# USB_Type-C_Test.net
KiCad netlist of a schematic drawn in EAGLE
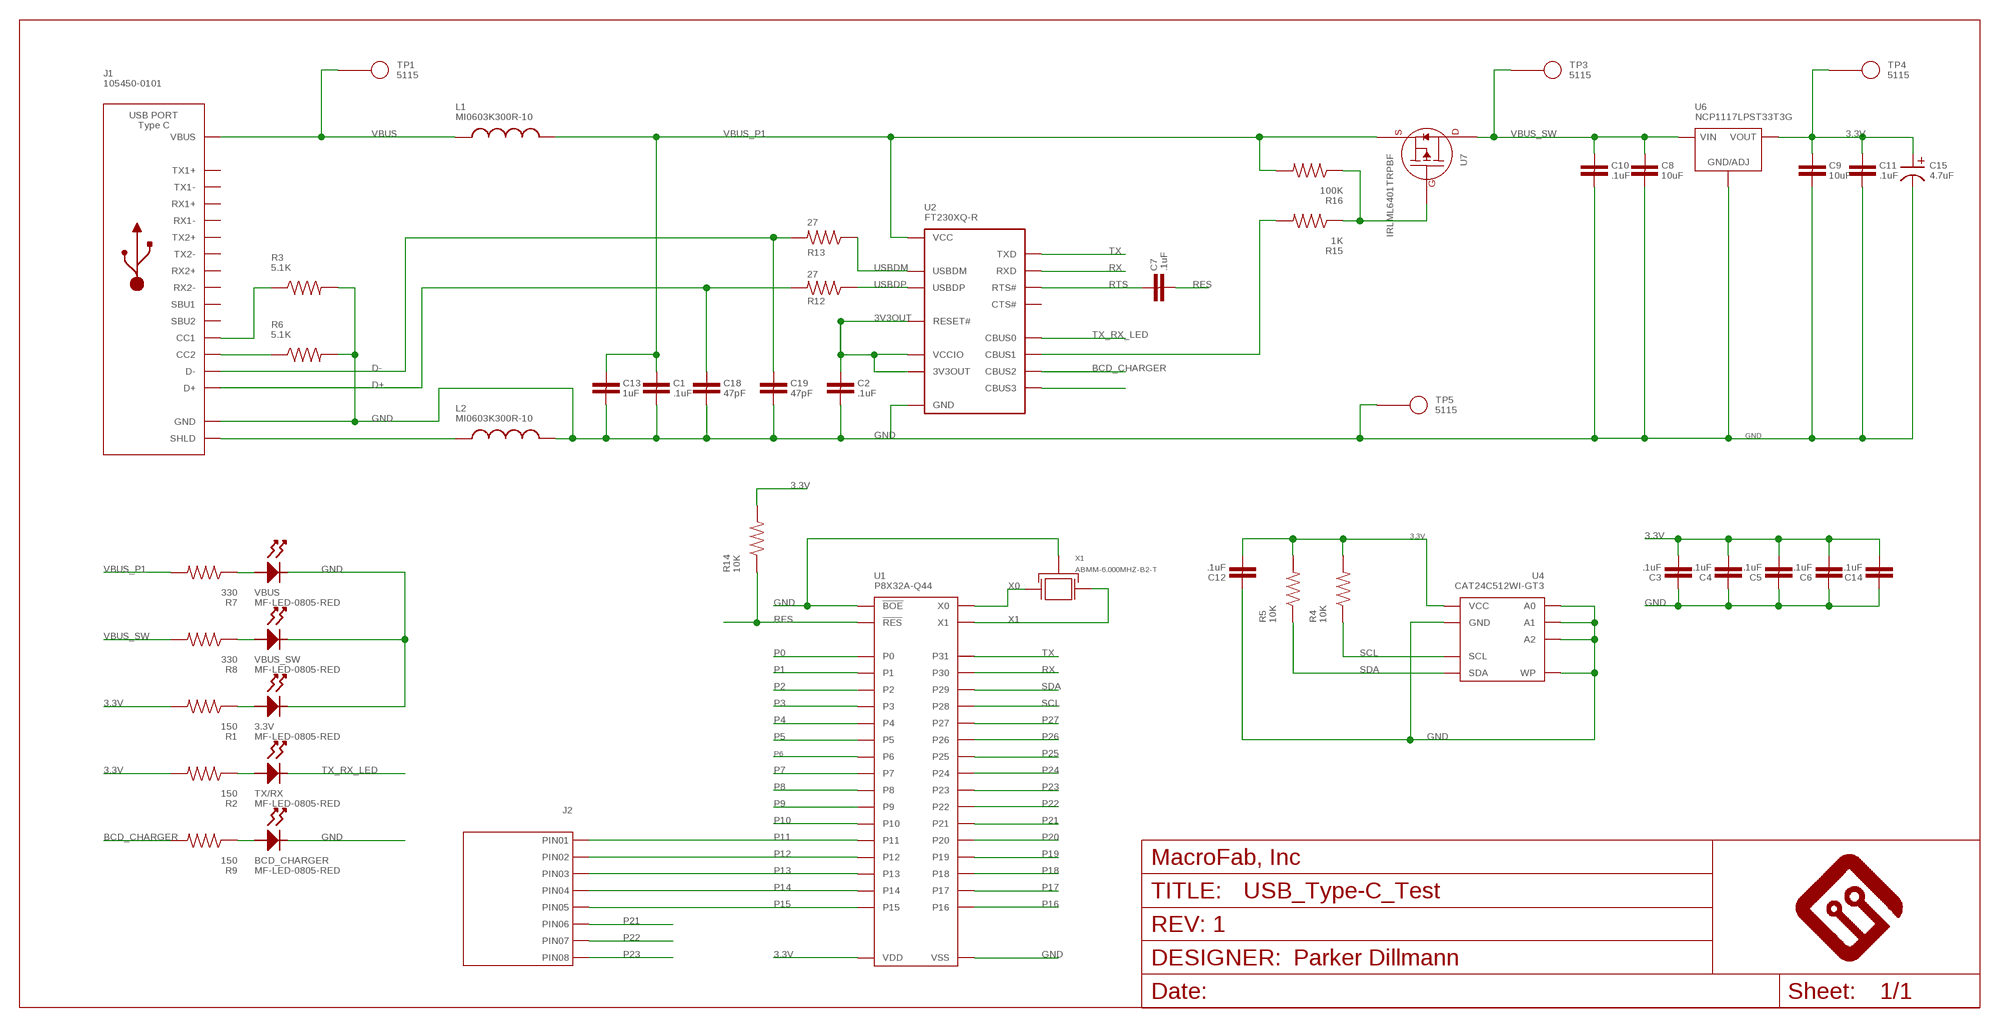
[diagram p0: schematic, sheet 1]

(export (version "E")
  (design (tool "Eeschema 10.0.6"))
  (components
    (comp (ref "3.3V")
      (value "MF-LED-0805-RED")
      (footprint "eagle-import:LED_0805")
      (libsource (lib "eagle-import") (part "LED_SINGLE_0805"))
    )
    (comp (ref "BCD_CHARGER")
      (value "MF-LED-0805-RED")
      (footprint "eagle-import:LED_0805")
      (libsource (lib "eagle-import") (part "LED_SINGLE_0805"))
    )
    (comp (ref "C1")
      (value ".1uF")
      (footprint "eagle-import:0603")
      (libsource (lib "eagle-import") (part "CAPACITOR_NON_POLAR_0603"))
    )
    (comp (ref "C2")
      (value ".1uF")
      (footprint "eagle-import:0603")
      (libsource (lib "eagle-import") (part "CAPACITOR_NON_POLAR_0603"))
    )
    (comp (ref "C3")
      (value ".1uF")
      (footprint "eagle-import:0603")
      (libsource (lib "eagle-import") (part "CAPACITOR_NON_POLAR_0603"))
    )
    (comp (ref "C4")
      (value ".1uF")
      (footprint "eagle-import:0603")
      (libsource (lib "eagle-import") (part "CAPACITOR_NON_POLAR_0603"))
    )
    (comp (ref "C5")
      (value ".1uF")
      (footprint "eagle-import:0603")
      (libsource (lib "eagle-import") (part "CAPACITOR_NON_POLAR_0603"))
    )
    (comp (ref "C6")
      (value ".1uF")
      (footprint "eagle-import:0603")
      (libsource (lib "eagle-import") (part "CAPACITOR_NON_POLAR_0603"))
    )
    (comp (ref "C7")
      (value ".1uF")
      (footprint "eagle-import:0603")
      (libsource (lib "eagle-import") (part "CAPACITOR_NON_POLAR_0603"))
    )
    (comp (ref "C8")
      (value "10uF")
      (footprint "eagle-import:1206")
      (libsource (lib "eagle-import") (part "CAPACITOR_NON_POLAR_1206"))
    )
    (comp (ref "C9")
      (value "10uF")
      (footprint "eagle-import:1206")
      (libsource (lib "eagle-import") (part "CAPACITOR_NON_POLAR_1206"))
    )
    (comp (ref "C10")
      (value ".1uF")
      (footprint "eagle-import:0603")
      (libsource (lib "eagle-import") (part "CAPACITOR_NON_POLAR_0603"))
    )
    (comp (ref "C11")
      (value ".1uF")
      (footprint "eagle-import:0603")
      (libsource (lib "eagle-import") (part "CAPACITOR_NON_POLAR_0603"))
    )
    (comp (ref "C12")
      (value ".1uF")
      (footprint "eagle-import:0603")
      (libsource (lib "eagle-import") (part "CAPACITOR_NON_POLAR_0603"))
    )
    (comp (ref "C13")
      (value "1uF")
      (footprint "eagle-import:0603")
      (libsource (lib "eagle-import") (part "CAPACITOR_NON_POLAR_0603"))
    )
    (comp (ref "C14")
      (value ".1uF")
      (footprint "eagle-import:0603")
      (libsource (lib "eagle-import") (part "CAPACITOR_NON_POLAR_0603"))
    )
    (comp (ref "C15")
      (value "4.7uF")
      (footprint "eagle-import:5MM_CAP_SMD")
      (libsource (lib "eagle-import") (part "CAPACITOR_POLARIZED_5MM_SMD"))
    )
    (comp (ref "C18")
      (value "47pF")
      (footprint "eagle-import:0603")
      (libsource (lib "eagle-import") (part "CAPACITOR_NON_POLAR_0603"))
    )
    (comp (ref "C19")
      (value "47pF")
      (footprint "eagle-import:0603")
      (libsource (lib "eagle-import") (part "CAPACITOR_NON_POLAR_0603"))
    )
    (comp (ref "FRAME1")
      (value "MF_FRAMEDEFAULT")
      (footprint "eagle-import:MF_FRAME_DEFAULT")
      (fields
        (field (name "HOUSEPART") "0")
        (field (name "DNAME") "Parker Dillmann")
        (field (name "REVNUM") "REV: 1")
      )
      (libsource (lib "eagle-import") (part "MF_FRAMEDEFAULT"))
    )
    (comp (ref "J1")
      (value "105450-0101")
      (footprint "eagle-import:105450-0101")
      (libsource (lib "eagle-import") (part "USB_TYPE-C_105450-0101"))
    )
    (comp (ref "J2")
      (value "CON_01X08_2.54MM_PIN_HEADER")
      (footprint "eagle-import:2.54MM_01X08_PIN_HEADER")
      (libsource (lib "eagle-import") (part "CON_01X08_2.54MM_PIN_HEADER"))
    )
    (comp (ref "L1")
      (value "MI0603K300R-10")
      (footprint "eagle-import:0603")
      (libsource (lib "eagle-import") (part "INDUCTOR_0603"))
    )
    (comp (ref "L2")
      (value "MI0603K300R-10")
      (footprint "eagle-import:0603")
      (libsource (lib "eagle-import") (part "INDUCTOR_0603"))
    )
    (comp (ref "R1")
      (value "150")
      (footprint "eagle-import:0603")
      (libsource (lib "eagle-import") (part "RESISTOR_0603"))
    )
    (comp (ref "R2")
      (value "150")
      (footprint "eagle-import:0603")
      (libsource (lib "eagle-import") (part "RESISTOR_0603"))
    )
    (comp (ref "R3")
      (value "5.1K")
      (footprint "eagle-import:0603")
      (libsource (lib "eagle-import") (part "RESISTOR_0603"))
    )
    (comp (ref "R4")
      (value "10K")
      (footprint "eagle-import:0603")
      (libsource (lib "eagle-import") (part "RESISTOR_0603"))
    )
    (comp (ref "R5")
      (value "10K")
      (footprint "eagle-import:0603")
      (libsource (lib "eagle-import") (part "RESISTOR_0603"))
    )
    (comp (ref "R6")
      (value "5.1K")
      (footprint "eagle-import:0603")
      (libsource (lib "eagle-import") (part "RESISTOR_0603"))
    )
    (comp (ref "R7")
      (value "330")
      (footprint "eagle-import:0603")
      (libsource (lib "eagle-import") (part "RESISTOR_0603"))
    )
    (comp (ref "R8")
      (value "330")
      (footprint "eagle-import:0603")
      (libsource (lib "eagle-import") (part "RESISTOR_0603"))
    )
    (comp (ref "R9")
      (value "150")
      (footprint "eagle-import:0603")
      (libsource (lib "eagle-import") (part "RESISTOR_0603"))
    )
    (comp (ref "R12")
      (value "27")
      (footprint "eagle-import:0603")
      (libsource (lib "eagle-import") (part "RESISTOR_0603"))
    )
    (comp (ref "R13")
      (value "27")
      (footprint "eagle-import:0603")
      (libsource (lib "eagle-import") (part "RESISTOR_0603"))
    )
    (comp (ref "R14")
      (value "10K")
      (footprint "eagle-import:0603")
      (libsource (lib "eagle-import") (part "RESISTOR_0603"))
    )
    (comp (ref "R15")
      (value "1K")
      (footprint "eagle-import:0603")
      (libsource (lib "eagle-import") (part "RESISTOR_0603"))
    )
    (comp (ref "R16")
      (value "100K")
      (footprint "eagle-import:0603")
      (libsource (lib "eagle-import") (part "RESISTOR_0603"))
    )
    (comp (ref "TP1")
      (value "5115")
      (footprint "eagle-import:KEYSTONE_5115-5119")
      (libsource (lib "eagle-import") (part "TEST_POINT_SINGLE_KEYSTONE_5115-5119"))
    )
    (comp (ref "TP3")
      (value "5115")
      (footprint "eagle-import:KEYSTONE_5115-5119")
      (libsource (lib "eagle-import") (part "TEST_POINT_SINGLE_KEYSTONE_5115-5119"))
    )
    (comp (ref "TP4")
      (value "5115")
      (footprint "eagle-import:KEYSTONE_5115-5119")
      (libsource (lib "eagle-import") (part "TEST_POINT_SINGLE_KEYSTONE_5115-5119"))
    )
    (comp (ref "TP5")
      (value "5115")
      (footprint "eagle-import:KEYSTONE_5115-5119")
      (libsource (lib "eagle-import") (part "TEST_POINT_SINGLE_KEYSTONE_5115-5119"))
    )
    (comp (ref "TX/RX")
      (value "MF-LED-0805-RED")
      (footprint "eagle-import:LED_0805")
      (libsource (lib "eagle-import") (part "LED_SINGLE_0805"))
    )
    (comp (ref "U1")
      (value "P8X32A-Q44")
      (footprint "eagle-import:P8X32A_LQFP-44")
      (libsource (lib "eagle-import") (part "P8X32A-Q44"))
    )
    (comp (ref "U2")
      (value "FT230XQ-R")
      (footprint "eagle-import:FT230X_QFN-16")
      (libsource (lib "eagle-import") (part "FT230XQ"))
    )
    (comp (ref "U4")
      (value "CAT24C512WI-GT3")
      (footprint "eagle-import:SOIC-8_W")
      (libsource (lib "eagle-import") (part "EEPROM_I2CSOIC-8_W"))
    )
    (comp (ref "U6")
      (value "NCP1117LPST33T3G")
      (footprint "eagle-import:SOT-223-3")
      (libsource (lib "eagle-import") (part "NCP1117LPST33T3G"))
    )
    (comp (ref "U7")
      (value "IRLML6401TRPBF")
      (footprint "eagle-import:SOT-23-3")
      (libsource (lib "eagle-import") (part "MOSFET_P-CHANNEL_SINGLE_SOT-23"))
    )
    (comp (ref "VBUS")
      (value "MF-LED-0805-RED")
      (footprint "eagle-import:LED_0805")
      (libsource (lib "eagle-import") (part "LED_SINGLE_0805"))
    )
    (comp (ref "VBUS_SW")
      (value "MF-LED-0805-RED")
      (footprint "eagle-import:LED_0805")
      (libsource (lib "eagle-import") (part "LED_SINGLE_0805"))
    )
    (comp (ref "X1")
      (value "ABMM-6.000MHZ-B2-T")
      (footprint "eagle-import:7MMX5MM")
      (libsource (lib "eagle-import") (part "XTL_7MMX5MM"))
    )
  )
  (nets
    (net (code "1") (name "/3.3V") (class "Default")
      (node (ref "C11") (pin "1") (pinfunction "1_1") (pintype "passive"))
      (node (ref "C12") (pin "2") (pinfunction "2_2") (pintype "passive"))
      (node (ref "C14") (pin "2") (pinfunction "2_2") (pintype "passive"))
      (node (ref "C15") (pin "P") (pinfunction "POS_P") (pintype "bidirectional"))
      (node (ref "C3") (pin "2") (pinfunction "2_2") (pintype "passive"))
      (node (ref "C4") (pin "2") (pinfunction "2_2") (pintype "passive"))
      (node (ref "C5") (pin "2") (pinfunction "2_2") (pintype "passive"))
      (node (ref "C6") (pin "2") (pinfunction "2_2") (pintype "passive"))
      (node (ref "C9") (pin "1") (pinfunction "1_1") (pintype "passive"))
      (node (ref "R1") (pin "2") (pinfunction "2_2") (pintype "passive"))
      (node (ref "R14") (pin "2") (pinfunction "2_2") (pintype "passive"))
      (node (ref "R2") (pin "2") (pinfunction "2_2") (pintype "passive"))
      (node (ref "R4") (pin "2") (pinfunction "2_2") (pintype "passive"))
      (node (ref "R5") (pin "2") (pinfunction "2_2") (pintype "passive"))
      (node (ref "TP4") (pin "P$1") (pinfunction "P$1_P$1") (pintype "bidirectional"))
      (node (ref "U1") (pin "18") (pinfunction "VDD_18") (pintype "bidirectional"))
      (node (ref "U1") (pin "30") (pinfunction "VDD_30") (pintype "bidirectional"))
      (node (ref "U1") (pin "40") (pinfunction "VDD_40") (pintype "bidirectional"))
      (node (ref "U1") (pin "8") (pinfunction "VDD_8") (pintype "bidirectional"))
      (node (ref "U4") (pin "8") (pinfunction "VCC_8") (pintype "bidirectional"))
      (node (ref "U6") (pin "P$1") (pinfunction "VOUT_P$1") (pintype "bidirectional"))
      (node (ref "U6") (pin "P$3") (pinfunction "VOUT_P$3") (pintype "bidirectional"))
    )
    (net (code "2") (name "/3V3OUT") (class "Default")
      (node (ref "C2") (pin "1") (pinfunction "1_1") (pintype "passive"))
      (node (ref "U2") (pin "1") (pinfunction "VCCIO_1") (pintype "bidirectional"))
      (node (ref "U2") (pin "8") (pinfunction "3V3OUT_8") (pintype "bidirectional"))
      (node (ref "U2") (pin "9") (pinfunction "RESET#_9") (pintype "bidirectional"))
    )
    (net (code "3") (name "/BCD_CHARGER") (class "Default")
      (node (ref "R9") (pin "2") (pinfunction "2_2") (pintype "passive"))
      (node (ref "U2") (pin "5") (pinfunction "CBUS2_5") (pintype "bidirectional"))
    )
    (net (code "4") (name "/D+") (class "Default")
      (node (ref "C18") (pin "1") (pinfunction "1_1") (pintype "passive"))
      (node (ref "J1") (pin "A6") (pinfunction "D+_A6") (pintype "bidirectional"))
      (node (ref "J1") (pin "B6") (pinfunction "D+_B6") (pintype "bidirectional"))
      (node (ref "R12") (pin "2") (pinfunction "2_2") (pintype "passive"))
    )
    (net (code "5") (name "/D-") (class "Default")
      (node (ref "C19") (pin "1") (pinfunction "1_1") (pintype "passive"))
      (node (ref "J1") (pin "A7") (pinfunction "D-_A7") (pintype "bidirectional"))
      (node (ref "J1") (pin "B7") (pinfunction "D-_B7") (pintype "bidirectional"))
      (node (ref "R13") (pin "2") (pinfunction "2_2") (pintype "passive"))
    )
    (net (code "6") (name "/GND") (class "Default")
      (node (ref "3.3V") (pin "CATHODE") (pinfunction "CATHODE_CATHODE") (pintype "bidirectional"))
      (node (ref "BCD_CHARGER") (pin "CATHODE") (pinfunction "CATHODE_CATHODE") (pintype "bidirectional"))
      (node (ref "C1") (pin "2") (pinfunction "2_2") (pintype "passive"))
      (node (ref "C10") (pin "2") (pinfunction "2_2") (pintype "passive"))
      (node (ref "C11") (pin "2") (pinfunction "2_2") (pintype "passive"))
      (node (ref "C12") (pin "1") (pinfunction "1_1") (pintype "passive"))
      (node (ref "C13") (pin "2") (pinfunction "2_2") (pintype "passive"))
      (node (ref "C14") (pin "1") (pinfunction "1_1") (pintype "passive"))
      (node (ref "C15") (pin "N") (pinfunction "NEG_N") (pintype "bidirectional"))
      (node (ref "C18") (pin "2") (pinfunction "2_2") (pintype "passive"))
      (node (ref "C19") (pin "2") (pinfunction "2_2") (pintype "passive"))
      (node (ref "C2") (pin "2") (pinfunction "2_2") (pintype "passive"))
      (node (ref "C3") (pin "1") (pinfunction "1_1") (pintype "passive"))
      (node (ref "C4") (pin "1") (pinfunction "1_1") (pintype "passive"))
      (node (ref "C5") (pin "1") (pinfunction "1_1") (pintype "passive"))
      (node (ref "C6") (pin "1") (pinfunction "1_1") (pintype "passive"))
      (node (ref "C8") (pin "2") (pinfunction "2_2") (pintype "passive"))
      (node (ref "C9") (pin "2") (pinfunction "2_2") (pintype "passive"))
      (node (ref "J1") (pin "A1") (pinfunction "GND_A1") (pintype "bidirectional"))
      (node (ref "J1") (pin "A12") (pinfunction "GND_A12") (pintype "bidirectional"))
      (node (ref "J1") (pin "B1") (pinfunction "GND_B1") (pintype "bidirectional"))
      (node (ref "J1") (pin "B12") (pinfunction "GND_B12") (pintype "bidirectional"))
      (node (ref "L2") (pin "2") (pinfunction "P$2_2") (pintype "bidirectional"))
      (node (ref "R3") (pin "2") (pinfunction "2_2") (pintype "passive"))
      (node (ref "R6") (pin "2") (pinfunction "2_2") (pintype "passive"))
      (node (ref "TP5") (pin "P$1") (pinfunction "P$1_P$1") (pintype "bidirectional"))
      (node (ref "U1") (pin "17") (pinfunction "VSS_17") (pintype "bidirectional"))
      (node (ref "U1") (pin "27") (pinfunction "VSS_27") (pintype "bidirectional"))
      (node (ref "U1") (pin "39") (pinfunction "VSS_39") (pintype "bidirectional"))
      (node (ref "U1") (pin "5") (pinfunction "VSS_5") (pintype "bidirectional"))
      (node (ref "U1") (pin "6") (pinfunction "~{BOE}_6") (pintype "bidirectional"))
      (node (ref "U2") (pin "13") (pinfunction "GND_13") (pintype "bidirectional"))
      (node (ref "U2") (pin "3") (pinfunction "GND_3") (pintype "bidirectional"))
      (node (ref "U2") (pin "PAD") (pinfunction "GND_PAD") (pintype "bidirectional"))
      (node (ref "U4") (pin "1") (pinfunction "A0_1") (pintype "bidirectional"))
      (node (ref "U4") (pin "2") (pinfunction "A1_2") (pintype "bidirectional"))
      (node (ref "U4") (pin "3") (pinfunction "A2_3") (pintype "bidirectional"))
      (node (ref "U4") (pin "4") (pinfunction "GND_4") (pintype "bidirectional"))
      (node (ref "U4") (pin "7") (pinfunction "WP_7") (pintype "bidirectional"))
      (node (ref "U6") (pin "P$2") (pinfunction "GND/ADJ_P$2") (pintype "bidirectional"))
      (node (ref "VBUS") (pin "CATHODE") (pinfunction "CATHODE_CATHODE") (pintype "bidirectional"))
      (node (ref "VBUS_SW") (pin "CATHODE") (pinfunction "CATHODE_CATHODE") (pintype "bidirectional"))
      (node (ref "X1") (pin "P$2") (pinfunction "GND_P$2") (pintype "bidirectional"))
      (node (ref "X1") (pin "P$4") (pinfunction "GND_P$4") (pintype "bidirectional"))
    )
    (net (code "7") (name "/P0") (class "Default")
      (node (ref "U1") (pin "41") (pinfunction "P0_41") (pintype "bidirectional"))
    )
    (net (code "8") (name "/P1") (class "Default")
      (node (ref "U1") (pin "42") (pinfunction "P1_42") (pintype "bidirectional"))
    )
    (net (code "9") (name "/P2") (class "Default")
      (node (ref "U1") (pin "43") (pinfunction "P2_43") (pintype "bidirectional"))
    )
    (net (code "10") (name "/P3") (class "Default")
      (node (ref "U1") (pin "44") (pinfunction "P3_44") (pintype "bidirectional"))
    )
    (net (code "11") (name "/P4") (class "Default")
      (node (ref "U1") (pin "1") (pinfunction "P4_1") (pintype "bidirectional"))
    )
    (net (code "12") (name "/P5") (class "Default")
      (node (ref "U1") (pin "2") (pinfunction "P5_2") (pintype "bidirectional"))
    )
    (net (code "13") (name "/P6") (class "Default")
      (node (ref "U1") (pin "3") (pinfunction "P6_3") (pintype "bidirectional"))
    )
    (net (code "14") (name "/P7") (class "Default")
      (node (ref "U1") (pin "4") (pinfunction "P7_4") (pintype "bidirectional"))
    )
    (net (code "15") (name "/P8") (class "Default")
      (node (ref "U1") (pin "9") (pinfunction "P8_9") (pintype "bidirectional"))
    )
    (net (code "16") (name "/P9") (class "Default")
      (node (ref "U1") (pin "10") (pinfunction "P9_10") (pintype "bidirectional"))
    )
    (net (code "17") (name "/P10") (class "Default")
      (node (ref "U1") (pin "11") (pinfunction "P10_11") (pintype "bidirectional"))
    )
    (net (code "18") (name "/P11") (class "Default")
      (node (ref "J2") (pin "1") (pinfunction "1_1") (pintype "bidirectional"))
      (node (ref "U1") (pin "12") (pinfunction "P11_12") (pintype "bidirectional"))
    )
    (net (code "19") (name "/P12") (class "Default")
      (node (ref "J2") (pin "2") (pinfunction "2_2") (pintype "bidirectional"))
      (node (ref "U1") (pin "13") (pinfunction "P12_13") (pintype "bidirectional"))
    )
    (net (code "20") (name "/P13") (class "Default")
      (node (ref "J2") (pin "3") (pinfunction "3_3") (pintype "bidirectional"))
      (node (ref "U1") (pin "14") (pinfunction "P13_14") (pintype "bidirectional"))
    )
    (net (code "21") (name "/P14") (class "Default")
      (node (ref "J2") (pin "4") (pinfunction "4_4") (pintype "bidirectional"))
      (node (ref "U1") (pin "15") (pinfunction "P14_15") (pintype "bidirectional"))
    )
    (net (code "22") (name "/P15") (class "Default")
      (node (ref "J2") (pin "5") (pinfunction "5_5") (pintype "bidirectional"))
      (node (ref "U1") (pin "16") (pinfunction "P15_16") (pintype "bidirectional"))
    )
    (net (code "23") (name "/P16") (class "Default")
      (node (ref "U1") (pin "19") (pinfunction "P16_19") (pintype "bidirectional"))
    )
    (net (code "24") (name "/P17") (class "Default")
      (node (ref "U1") (pin "20") (pinfunction "P17_20") (pintype "bidirectional"))
    )
    (net (code "25") (name "/P18") (class "Default")
      (node (ref "U1") (pin "21") (pinfunction "P18_21") (pintype "bidirectional"))
    )
    (net (code "26") (name "/P19") (class "Default")
      (node (ref "U1") (pin "22") (pinfunction "P19_22") (pintype "bidirectional"))
    )
    (net (code "27") (name "/P20") (class "Default")
      (node (ref "U1") (pin "23") (pinfunction "P20_23") (pintype "bidirectional"))
    )
    (net (code "28") (name "/P21") (class "Default")
      (node (ref "J2") (pin "6") (pinfunction "6_6") (pintype "bidirectional"))
      (node (ref "U1") (pin "24") (pinfunction "P21_24") (pintype "bidirectional"))
    )
    (net (code "29") (name "/P22") (class "Default")
      (node (ref "J2") (pin "7") (pinfunction "7_7") (pintype "bidirectional"))
      (node (ref "U1") (pin "25") (pinfunction "P22_25") (pintype "bidirectional"))
    )
    (net (code "30") (name "/P23") (class "Default")
      (node (ref "J2") (pin "8") (pinfunction "8_8") (pintype "bidirectional"))
      (node (ref "U1") (pin "26") (pinfunction "P23_26") (pintype "bidirectional"))
    )
    (net (code "31") (name "/P24") (class "Default")
      (node (ref "U1") (pin "31") (pinfunction "P24_31") (pintype "bidirectional"))
    )
    (net (code "32") (name "/P25") (class "Default")
      (node (ref "U1") (pin "32") (pinfunction "P25_32") (pintype "bidirectional"))
    )
    (net (code "33") (name "/P26") (class "Default")
      (node (ref "U1") (pin "33") (pinfunction "P26_33") (pintype "bidirectional"))
    )
    (net (code "34") (name "/P27") (class "Default")
      (node (ref "U1") (pin "34") (pinfunction "P27_34") (pintype "bidirectional"))
    )
    (net (code "35") (name "/RES") (class "Default")
      (node (ref "C7") (pin "2") (pinfunction "2_2") (pintype "passive"))
      (node (ref "R14") (pin "1") (pinfunction "1_1") (pintype "passive"))
      (node (ref "U1") (pin "7") (pinfunction "~{RES}_7") (pintype "bidirectional"))
    )
    (net (code "36") (name "/RTS") (class "Default")
      (node (ref "C7") (pin "1") (pinfunction "1_1") (pintype "passive"))
      (node (ref "U2") (pin "16") (pinfunction "RTS#_16") (pintype "bidirectional"))
    )
    (net (code "37") (name "/RX") (class "Default")
      (node (ref "U1") (pin "37") (pinfunction "P30_37") (pintype "bidirectional"))
      (node (ref "U2") (pin "2") (pinfunction "RXD_2") (pintype "bidirectional"))
    )
    (net (code "38") (name "/SCL") (class "Default")
      (node (ref "R4") (pin "1") (pinfunction "1_1") (pintype "passive"))
      (node (ref "U1") (pin "35") (pinfunction "P28_35") (pintype "bidirectional"))
      (node (ref "U4") (pin "6") (pinfunction "SCL_6") (pintype "bidirectional"))
    )
    (net (code "39") (name "/SDA") (class "Default")
      (node (ref "R5") (pin "1") (pinfunction "1_1") (pintype "passive"))
      (node (ref "U1") (pin "36") (pinfunction "P29_36") (pintype "bidirectional"))
      (node (ref "U4") (pin "5") (pinfunction "SDA_5") (pintype "bidirectional"))
    )
    (net (code "40") (name "/TX") (class "Default")
      (node (ref "U1") (pin "38") (pinfunction "P31_38") (pintype "bidirectional"))
      (node (ref "U2") (pin "15") (pinfunction "TXD_15") (pintype "bidirectional"))
    )
    (net (code "41") (name "/TX_RX_LED") (class "Default")
      (node (ref "TX/RX") (pin "CATHODE") (pinfunction "CATHODE_CATHODE") (pintype "bidirectional"))
      (node (ref "U2") (pin "12") (pinfunction "CBUS0_12") (pintype "bidirectional"))
    )
    (net (code "42") (name "/USBDM") (class "Default")
      (node (ref "R13") (pin "1") (pinfunction "1_1") (pintype "passive"))
      (node (ref "U2") (pin "7") (pinfunction "USBDM_7") (pintype "bidirectional"))
    )
    (net (code "43") (name "/USBDP") (class "Default")
      (node (ref "R12") (pin "1") (pinfunction "1_1") (pintype "passive"))
      (node (ref "U2") (pin "6") (pinfunction "USBDP_6") (pintype "bidirectional"))
    )
    (net (code "44") (name "/VBUS") (class "Default")
      (node (ref "J1") (pin "A4") (pinfunction "VBUS_A4") (pintype "bidirectional"))
      (node (ref "J1") (pin "A9") (pinfunction "VBUS_A9") (pintype "bidirectional"))
      (node (ref "J1") (pin "B4") (pinfunction "VBUS_B4") (pintype "bidirectional"))
      (node (ref "J1") (pin "B9") (pinfunction "VBUS_B9") (pintype "bidirectional"))
      (node (ref "L1") (pin "1") (pinfunction "P$1_1") (pintype "bidirectional"))
      (node (ref "TP1") (pin "P$1") (pinfunction "P$1_P$1") (pintype "bidirectional"))
    )
    (net (code "45") (name "/VBUS_P1") (class "Default")
      (node (ref "C1") (pin "1") (pinfunction "1_1") (pintype "passive"))
      (node (ref "C13") (pin "1") (pinfunction "1_1") (pintype "passive"))
      (node (ref "L1") (pin "2") (pinfunction "P$2_2") (pintype "bidirectional"))
      (node (ref "R16") (pin "2") (pinfunction "2_2") (pintype "passive"))
      (node (ref "R7") (pin "2") (pinfunction "2_2") (pintype "passive"))
      (node (ref "U2") (pin "10") (pinfunction "VCC_10") (pintype "bidirectional"))
      (node (ref "U7") (pin "2") (pinfunction "SOURCE_2") (pintype "bidirectional"))
    )
    (net (code "46") (name "/VBUS_SW") (class "Default")
      (node (ref "C10") (pin "1") (pinfunction "1_1") (pintype "passive"))
      (node (ref "C8") (pin "1") (pinfunction "1_1") (pintype "passive"))
      (node (ref "R8") (pin "2") (pinfunction "2_2") (pintype "passive"))
      (node (ref "TP3") (pin "P$1") (pinfunction "P$1_P$1") (pintype "bidirectional"))
      (node (ref "U6") (pin "P$4") (pinfunction "VIN_P$4") (pintype "bidirectional"))
      (node (ref "U7") (pin "3") (pinfunction "DRAIN_3") (pintype "bidirectional"))
    )
    (net (code "47") (name "/X0") (class "Default")
      (node (ref "U1") (pin "29") (pinfunction "X0_29") (pintype "bidirectional"))
      (node (ref "X1") (pin "P$3") (pinfunction "X1_P$3") (pintype "bidirectional"))
    )
    (net (code "48") (name "/X1") (class "Default")
      (node (ref "U1") (pin "28") (pinfunction "X1_28") (pintype "bidirectional"))
      (node (ref "X1") (pin "P$1") (pinfunction "X0_P$1") (pintype "bidirectional"))
    )
    (net (code "49") (name "Net-(3.3V-PadANODE)") (class "Default")
      (node (ref "3.3V") (pin "ANODE") (pinfunction "ANODE_ANODE") (pintype "bidirectional"))
      (node (ref "R1") (pin "1") (pinfunction "1_1") (pintype "passive"))
    )
    (net (code "50") (name "Net-(BCD_CHARGER-PadANODE)") (class "Default")
      (node (ref "BCD_CHARGER") (pin "ANODE") (pinfunction "ANODE_ANODE") (pintype "bidirectional"))
      (node (ref "R9") (pin "1") (pinfunction "1_1") (pintype "passive"))
    )
    (net (code "51") (name "Net-(J1-CC1)") (class "Default")
      (node (ref "J1") (pin "A5") (pinfunction "CC1_A5") (pintype "bidirectional"))
      (node (ref "R3") (pin "1") (pinfunction "1_1") (pintype "passive"))
    )
    (net (code "52") (name "Net-(J1-CC2)") (class "Default")
      (node (ref "J1") (pin "B5") (pinfunction "CC2_B5") (pintype "bidirectional"))
      (node (ref "R6") (pin "1") (pinfunction "1_1") (pintype "passive"))
    )
    (net (code "53") (name "Net-(L2-P$1)") (class "Default")
      (node (ref "J1") (pin "S_T1") (pinfunction "SHLD_S_T1") (pintype "bidirectional"))
      (node (ref "J1") (pin "S_T2") (pinfunction "SHLD_S_T2") (pintype "bidirectional"))
      (node (ref "J1") (pin "S_T3") (pinfunction "SHLD_S_T3") (pintype "bidirectional"))
      (node (ref "J1") (pin "S_T4") (pinfunction "SHLD_S_T4") (pintype "bidirectional"))
      (node (ref "L2") (pin "1") (pinfunction "P$1_1") (pintype "bidirectional"))
    )
    (net (code "54") (name "Net-(R2-Pad1)") (class "Default")
      (node (ref "R2") (pin "1") (pinfunction "1_1") (pintype "passive"))
      (node (ref "TX/RX") (pin "ANODE") (pinfunction "ANODE_ANODE") (pintype "bidirectional"))
    )
    (net (code "55") (name "Net-(R7-Pad1)") (class "Default")
      (node (ref "R7") (pin "1") (pinfunction "1_1") (pintype "passive"))
      (node (ref "VBUS") (pin "ANODE") (pinfunction "ANODE_ANODE") (pintype "bidirectional"))
    )
    (net (code "56") (name "Net-(R8-Pad1)") (class "Default")
      (node (ref "R8") (pin "1") (pinfunction "1_1") (pintype "passive"))
      (node (ref "VBUS_SW") (pin "ANODE") (pinfunction "ANODE_ANODE") (pintype "bidirectional"))
    )
    (net (code "57") (name "Net-(U2-CBUS1)") (class "Default")
      (node (ref "R15") (pin "2") (pinfunction "2_2") (pintype "passive"))
      (node (ref "U2") (pin "11") (pinfunction "CBUS1_11") (pintype "bidirectional"))
    )
    (net (code "58") (name "Net-(U7-GATE)") (class "Default")
      (node (ref "R15") (pin "1") (pinfunction "1_1") (pintype "passive"))
      (node (ref "R16") (pin "1") (pinfunction "1_1") (pintype "passive"))
      (node (ref "U7") (pin "1") (pinfunction "GATE_1") (pintype "bidirectional"))
    )
    (net (code "59") (name "unconnected-(J1-RX1+-PadB11)") (class "Default")
      (node (ref "J1") (pin "B11") (pinfunction "RX1+_B11") (pintype "bidirectional"))
    )
    (net (code "60") (name "unconnected-(J1-RX1--PadB10)") (class "Default")
      (node (ref "J1") (pin "B10") (pinfunction "RX1-_B10") (pintype "bidirectional"))
    )
    (net (code "61") (name "unconnected-(J1-RX2+-PadA11)") (class "Default")
      (node (ref "J1") (pin "A11") (pinfunction "RX2+_A11") (pintype "bidirectional"))
    )
    (net (code "62") (name "unconnected-(J1-RX2--PadA10)") (class "Default")
      (node (ref "J1") (pin "A10") (pinfunction "RX2-_A10") (pintype "bidirectional"))
    )
    (net (code "63") (name "unconnected-(J1-SBU1-PadA8)") (class "Default")
      (node (ref "J1") (pin "A8") (pinfunction "SBU1_A8") (pintype "bidirectional"))
    )
    (net (code "64") (name "unconnected-(J1-SBU2-PadB8)") (class "Default")
      (node (ref "J1") (pin "B8") (pinfunction "SBU2_B8") (pintype "bidirectional"))
    )
    (net (code "65") (name "unconnected-(J1-TX1+-PadA2)") (class "Default")
      (node (ref "J1") (pin "A2") (pinfunction "TX1+_A2") (pintype "bidirectional"))
    )
    (net (code "66") (name "unconnected-(J1-TX1--PadA3)") (class "Default")
      (node (ref "J1") (pin "A3") (pinfunction "TX1-_A3") (pintype "bidirectional"))
    )
    (net (code "67") (name "unconnected-(J1-TX2+-PadB2)") (class "Default")
      (node (ref "J1") (pin "B2") (pinfunction "TX2+_B2") (pintype "bidirectional"))
    )
    (net (code "68") (name "unconnected-(J1-TX2--PadB3)") (class "Default")
      (node (ref "J1") (pin "B3") (pinfunction "TX2-_B3") (pintype "bidirectional"))
    )
    (net (code "69") (name "unconnected-(U2-CBUS3-Pad14)") (class "Default")
      (node (ref "U2") (pin "14") (pinfunction "CBUS3_14") (pintype "bidirectional"))
    )
    (net (code "70") (name "unconnected-(U2-CTS#-Pad4)") (class "Default")
      (node (ref "U2") (pin "4") (pinfunction "CTS#_4") (pintype "bidirectional"))
    )
  )
)
